# ESP32_wroom_board.net
KiCad netlist of a schematic drawn in Altium Designer
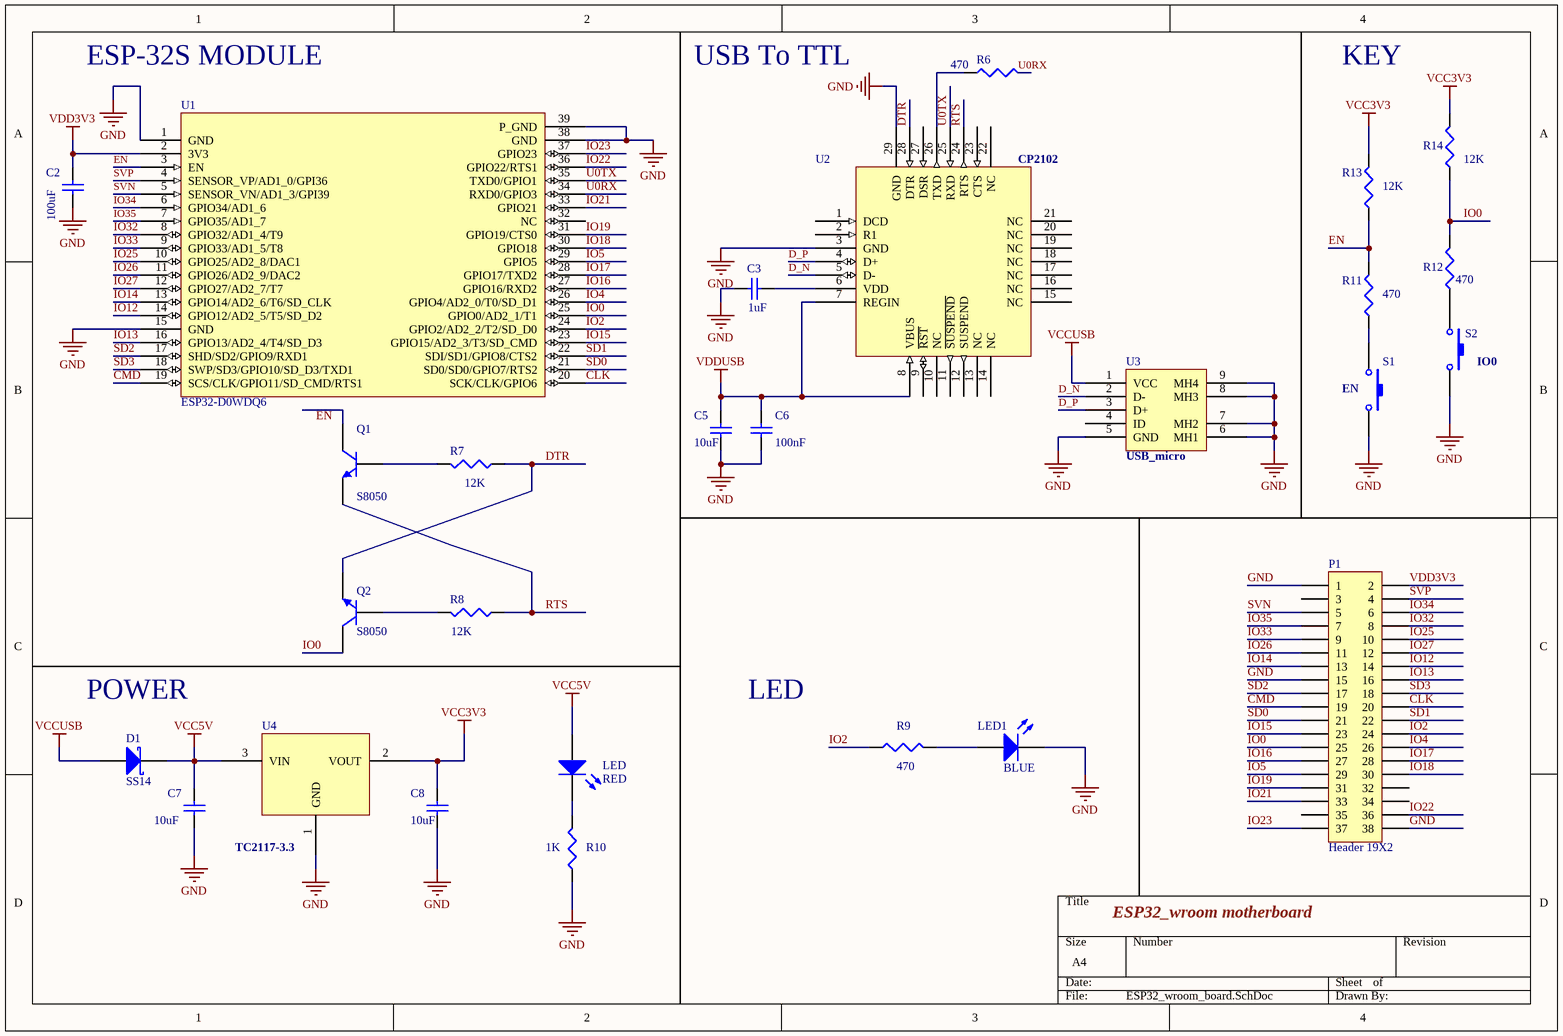
[diagram p0: ESP32_wroom_board.SchDoc]

(export (version "E")
  (design (tool "Eeschema 10.0.6"))
  (components
    (comp (ref "C2")
      (value "100uF")
      (footprint "1608[0603]")
      (description "Capacitor (Semiconductor SIM Model)")
      (fields (field (name "Comment") "Cap Semi") (field (name "PUBLISHER") "Altium Limited"))
      (libsource (lib "Miscellaneous Devices") (part "Cap Semi"))
    )
    (comp (ref "C3")
      (value "1uF")
      (footprint "1608[0603]")
      (description "Capacitor (Semiconductor SIM Model)")
      (fields (field (name "Comment") "Cap Semi") (field (name "PUBLISHER") "Altium Limited"))
      (libsource (lib "Miscellaneous Devices") (part "Cap Semi"))
    )
    (comp (ref "C5")
      (value "10uF")
      (footprint "1608[0603]")
      (description "Capacitor (Semiconductor SIM Model)")
      (fields (field (name "Comment") "Cap Semi") (field (name "PUBLISHER") "Altium Limited"))
      (libsource (lib "Miscellaneous Devices") (part "Cap Semi"))
    )
    (comp (ref "C6")
      (value "100nF")
      (footprint "1608[0603]")
      (description "Capacitor (Semiconductor SIM Model)")
      (fields (field (name "Comment") "Cap Semi") (field (name "PUBLISHER") "Altium Limited"))
      (libsource (lib "Miscellaneous Devices") (part "Cap Semi"))
    )
    (comp (ref "C7")
      (value "10uF")
      (footprint "1608[0603]")
      (description "Capacitor (Semiconductor SIM Model)")
      (fields (field (name "Comment") "Cap Semi") (field (name "PUBLISHER") "Altium Limited"))
      (libsource (lib "Miscellaneous Devices") (part "Cap Semi"))
    )
    (comp (ref "C8")
      (value "10uF")
      (footprint "1608[0603]")
      (description "Capacitor (Semiconductor SIM Model)")
      (fields (field (name "Comment") "Cap Semi") (field (name "PUBLISHER") "Altium Limited"))
      (libsource (lib "Miscellaneous Devices") (part "Cap Semi"))
    )
    (comp (ref "D1")
      (value "SS14")
      (footprint "SOD323")
      (description "Schottky Barrier Diode")
      (fields (field (name "PUBLISHER") "Altium Limited"))
      (libsource (lib "Philips Discrete Diode - Schottky") (part "BAT760"))
    )
    (comp (ref "LED")
      (value "RED")
      (footprint "3.2X1.6X1.1")
      (description "Typical RED, GREEN, YELLOW, AMBER GaAs LED")
      (fields (field (name "PUBLISHER") "Altium Limited"))
      (libsource (lib "Miscellaneous Devices") (part "LED2"))
    )
    (comp (ref "LED1")
      (value "BLUE")
      (footprint "3.2X1.6X1.1")
      (description "Typical RED, GREEN, YELLOW, AMBER GaAs LED")
      (fields (field (name "PUBLISHER") "Altium Limited"))
      (libsource (lib "Miscellaneous Devices") (part "LED2"))
    )
    (comp (ref "P1")
      (value "Header 19X2")
      (footprint "HDR2X19")
      (description "Header, 19-Pin, Dual row")
      (fields (field (name "PUBLISHER") "Altium Limited"))
      (libsource (lib "Miscellaneous Connectors") (part "Header 19X2"))
    )
    (comp (ref "Q1")
      (value "S8050")
      (footprint "SOT-23A_N")
      (description "NPN General Purpose Amplifier")
      (fields (field (name "PUBLISHER") "Altium Limited"))
      (libsource (lib "FSC Discrete BJT") (part "BCW65C"))
    )
    (comp (ref "Q2")
      (value "S8050")
      (footprint "SOT-23A_N")
      (description "NPN General Purpose Amplifier")
      (fields (field (name "PUBLISHER") "Altium Limited"))
      (libsource (lib "FSC Discrete BJT") (part "BCW65C"))
    )
    (comp (ref "R6")
      (value "470")
      (footprint "J1-0603")
      (description "Resistor")
      (fields (field (name "Comment") "Res3") (field (name "PUBLISHER") "Altium Limited"))
      (libsource (lib "Miscellaneous Devices") (part "Res3"))
    )
    (comp (ref "R7")
      (value "12K")
      (footprint "J1-0603")
      (description "Resistor")
      (fields (field (name "Comment") "Res3") (field (name "PUBLISHER") "Altium Limited"))
      (libsource (lib "Miscellaneous Devices") (part "Res3"))
    )
    (comp (ref "R8")
      (value "12K")
      (footprint "J1-0603")
      (description "Resistor")
      (fields (field (name "Comment") "Res3") (field (name "PUBLISHER") "Altium Limited"))
      (libsource (lib "Miscellaneous Devices") (part "Res3"))
    )
    (comp (ref "R9")
      (value "470")
      (footprint "J1-0603")
      (description "Resistor")
      (fields (field (name "Comment") "Res3") (field (name "PUBLISHER") "Altium Limited"))
      (libsource (lib "Miscellaneous Devices") (part "Res3"))
    )
    (comp (ref "R10")
      (value "1K")
      (footprint "J1-0603")
      (description "Resistor")
      (fields (field (name "Comment") "Res3") (field (name "PUBLISHER") "Altium Limited"))
      (libsource (lib "Miscellaneous Devices") (part "Res3"))
    )
    (comp (ref "R11")
      (value "470")
      (footprint "J1-0603")
      (description "Resistor")
      (fields (field (name "Comment") "Res3") (field (name "PUBLISHER") "Altium Limited"))
      (libsource (lib "Miscellaneous Devices") (part "Res3"))
    )
    (comp (ref "R12")
      (value "470")
      (footprint "J1-0603")
      (description "Resistor")
      (fields (field (name "Comment") "Res3") (field (name "PUBLISHER") "Altium Limited"))
      (libsource (lib "Miscellaneous Devices") (part "Res3"))
    )
    (comp (ref "R13")
      (value "12K")
      (footprint "J1-0603")
      (description "Resistor")
      (fields (field (name "Comment") "Res3") (field (name "PUBLISHER") "Altium Limited"))
      (libsource (lib "Miscellaneous Devices") (part "Res3"))
    )
    (comp (ref "R14")
      (value "12K")
      (footprint "J1-0603")
      (description "Resistor")
      (fields (field (name "Comment") "Res3") (field (name "PUBLISHER") "Altium Limited"))
      (libsource (lib "Miscellaneous Devices") (part "Res3"))
    )
    (comp (ref "S1")
      (value "SW-PB")
      (footprint "SPST-2")
      (description "Switch")
      (fields (field (name "PUBLISHER") "Altium Limited"))
      (libsource (lib "Miscellaneous Devices") (part "SW-PB"))
    )
    (comp (ref "S2")
      (value "SW-PB")
      (footprint "SPST-2")
      (description "Switch")
      (fields (field (name "PUBLISHER") "Altium Limited"))
      (libsource (lib "Miscellaneous Devices") (part "SW-PB"))
    )
    (comp (ref "U1")
      (value "ESP32-D0WDQ6")
      (footprint "ESP32WROOM32D")
      (libsource (lib "Custom_components") (part "ESP32-WROOM-32"))
    )
    (comp (ref "U2")
      (value "CP2102")
      (description "USB Interface IC USB to UART Bridge QFN28")
      (libsource (lib "Custom_components") (part "CP2102"))
    )
    (comp (ref "U3")
      (value "USB_micro")
      (description "USB_micro_5S_B")
      (libsource (lib "Custom_components") (part "USB_micro"))
    )
    (comp (ref "U4")
      (value "TC2117-3.3")
      (footprint "*SOT230P700X180-4N")
      (description "LDO Voltage Regulators 800mA Fixed Output")
      (libsource (lib "Custom_components") (part "TC2117-3.3VDBTR"))
    )
  )
  (nets
    (net (code "1") (name "/CLK") (class "Default")
      (node (ref "P1") (pin "20") (pinfunction "20_20") (pintype "passive"))
      (node (ref "U1") (pin "20") (pinfunction "SCK/CLK/GPIO6_20") (pintype "bidirectional"))
    )
    (net (code "2") (name "/CMD") (class "Default")
      (node (ref "P1") (pin "19") (pinfunction "19_19") (pintype "passive"))
      (node (ref "U1") (pin "19") (pinfunction "SCS/CLK/GPIO11/SD_CMD/RTS1_19") (pintype "bidirectional"))
    )
    (net (code "3") (name "/DTR") (class "Default")
      (node (ref "Q2") (pin "2") (pinfunction "E_2") (pintype "passive"))
      (node (ref "R7") (pin "1") (pinfunction "1_1") (pintype "passive"))
      (node (ref "U2") (pin "28") (pinfunction "DTR_28") (pintype "input"))
    )
    (net (code "4") (name "/D_N") (class "Default")
      (node (ref "U2") (pin "5") (pinfunction "D-_5") (pintype "bidirectional"))
      (node (ref "U3") (pin "2") (pinfunction "D-_2") (pintype "passive"))
    )
    (net (code "5") (name "/D_P") (class "Default")
      (node (ref "U2") (pin "4") (pinfunction "D+_4") (pintype "bidirectional"))
      (node (ref "U3") (pin "3") (pinfunction "D+_3") (pintype "passive"))
    )
    (net (code "6") (name "/EN") (class "Default")
      (node (ref "R11") (pin "2") (pinfunction "2_2") (pintype "passive"))
      (node (ref "R13") (pin "1") (pinfunction "1_1") (pintype "passive"))
      (node (ref "U1") (pin "3") (pinfunction "EN_3") (pintype "input"))
    )
    (net (code "7") (name "/IO0") (class "Default")
      (node (ref "P1") (pin "25") (pinfunction "25_25") (pintype "passive"))
      (node (ref "Q2") (pin "3") (pinfunction "C_3") (pintype "passive"))
      (node (ref "R12") (pin "2") (pinfunction "2_2") (pintype "passive"))
      (node (ref "R14") (pin "1") (pinfunction "1_1") (pintype "passive"))
      (node (ref "U1") (pin "25") (pinfunction "GPIO0/AD2_1/T1_25") (pintype "bidirectional"))
    )
    (net (code "8") (name "/IO2") (class "Default")
      (node (ref "P1") (pin "24") (pinfunction "24_24") (pintype "passive"))
      (node (ref "R9") (pin "1") (pinfunction "1_1") (pintype "passive"))
      (node (ref "U1") (pin "24") (pinfunction "GPIO2/AD2_2/T2/SD_D0_24") (pintype "bidirectional"))
    )
    (net (code "9") (name "/IO4") (class "Default")
      (node (ref "P1") (pin "26") (pinfunction "26_26") (pintype "passive"))
      (node (ref "U1") (pin "26") (pinfunction "GPIO4/AD2_0/T0/SD_D1_26") (pintype "bidirectional"))
    )
    (net (code "10") (name "/IO5") (class "Default")
      (node (ref "P1") (pin "29") (pinfunction "29_29") (pintype "passive"))
      (node (ref "U1") (pin "29") (pinfunction "GPIO5_29") (pintype "bidirectional"))
    )
    (net (code "11") (name "/IO12") (class "Default")
      (node (ref "P1") (pin "14") (pinfunction "14_14") (pintype "passive"))
      (node (ref "U1") (pin "14") (pinfunction "GPIO12/AD2_5/T5/SD_D2_14") (pintype "bidirectional"))
    )
    (net (code "12") (name "/IO13") (class "Default")
      (node (ref "P1") (pin "16") (pinfunction "16_16") (pintype "passive"))
      (node (ref "U1") (pin "16") (pinfunction "GPIO13/AD2_4/T4/SD_D3_16") (pintype "bidirectional"))
    )
    (net (code "13") (name "/IO14") (class "Default")
      (node (ref "P1") (pin "13") (pinfunction "13_13") (pintype "passive"))
      (node (ref "U1") (pin "13") (pinfunction "GPIO14/AD2_6/T6/SD_CLK_13") (pintype "bidirectional"))
    )
    (net (code "14") (name "/IO15") (class "Default")
      (node (ref "P1") (pin "23") (pinfunction "23_23") (pintype "passive"))
      (node (ref "U1") (pin "23") (pinfunction "GPIO15/AD2_3/T3/SD_CMD_23") (pintype "bidirectional"))
    )
    (net (code "15") (name "/IO16") (class "Default")
      (node (ref "P1") (pin "27") (pinfunction "27_27") (pintype "passive"))
      (node (ref "U1") (pin "27") (pinfunction "GPIO16/RXD2_27") (pintype "bidirectional"))
    )
    (net (code "16") (name "/IO17") (class "Default")
      (node (ref "P1") (pin "28") (pinfunction "28_28") (pintype "passive"))
      (node (ref "U1") (pin "28") (pinfunction "GPIO17/TXD2_28") (pintype "bidirectional"))
    )
    (net (code "17") (name "/IO18") (class "Default")
      (node (ref "P1") (pin "30") (pinfunction "30_30") (pintype "passive"))
      (node (ref "U1") (pin "30") (pinfunction "GPIO18_30") (pintype "bidirectional"))
    )
    (net (code "18") (name "/IO19") (class "Default")
      (node (ref "P1") (pin "31") (pinfunction "31_31") (pintype "passive"))
      (node (ref "U1") (pin "31") (pinfunction "GPIO19/CTS0_31") (pintype "bidirectional"))
    )
    (net (code "19") (name "/IO21") (class "Default")
      (node (ref "P1") (pin "33") (pinfunction "33_33") (pintype "passive"))
      (node (ref "U1") (pin "33") (pinfunction "GPIO21_33") (pintype "bidirectional"))
    )
    (net (code "20") (name "/IO22") (class "Default")
      (node (ref "P1") (pin "36") (pinfunction "36_36") (pintype "passive"))
      (node (ref "U1") (pin "36") (pinfunction "GPIO22/RTS1_36") (pintype "bidirectional"))
    )
    (net (code "21") (name "/IO23") (class "Default")
      (node (ref "P1") (pin "37") (pinfunction "37_37") (pintype "passive"))
      (node (ref "U1") (pin "37") (pinfunction "GPIO23_37") (pintype "bidirectional"))
    )
    (net (code "22") (name "/IO25") (class "Default")
      (node (ref "P1") (pin "10") (pinfunction "10_10") (pintype "passive"))
      (node (ref "U1") (pin "10") (pinfunction "GPIO25/AD2_8/DAC1_10") (pintype "bidirectional"))
    )
    (net (code "23") (name "/IO26") (class "Default")
      (node (ref "P1") (pin "11") (pinfunction "11_11") (pintype "passive"))
      (node (ref "U1") (pin "11") (pinfunction "GPIO26/AD2_9/DAC2_11") (pintype "bidirectional"))
    )
    (net (code "24") (name "/IO27") (class "Default")
      (node (ref "P1") (pin "12") (pinfunction "12_12") (pintype "passive"))
      (node (ref "U1") (pin "12") (pinfunction "GPIO27/AD2_7/T7_12") (pintype "bidirectional"))
    )
    (net (code "25") (name "/IO32") (class "Default")
      (node (ref "P1") (pin "8") (pinfunction "8_8") (pintype "passive"))
      (node (ref "U1") (pin "8") (pinfunction "GPIO32/AD1_4/T9_8") (pintype "bidirectional"))
    )
    (net (code "26") (name "/IO33") (class "Default")
      (node (ref "P1") (pin "9") (pinfunction "9_9") (pintype "passive"))
      (node (ref "U1") (pin "9") (pinfunction "GPIO33/AD1_5/T8_9") (pintype "bidirectional"))
    )
    (net (code "27") (name "/IO34") (class "Default")
      (node (ref "P1") (pin "6") (pinfunction "6_6") (pintype "passive"))
      (node (ref "U1") (pin "6") (pinfunction "GPIO34/AD1_6_6") (pintype "input"))
    )
    (net (code "28") (name "/IO35") (class "Default")
      (node (ref "P1") (pin "7") (pinfunction "7_7") (pintype "passive"))
      (node (ref "U1") (pin "7") (pinfunction "GPIO35/AD1_7_7") (pintype "input"))
    )
    (net (code "29") (name "/RTS") (class "Default")
      (node (ref "Q1") (pin "2") (pinfunction "E_2") (pintype "passive"))
      (node (ref "R8") (pin "1") (pinfunction "1_1") (pintype "passive"))
      (node (ref "U2") (pin "24") (pinfunction "RTS_24") (pintype "output"))
    )
    (net (code "30") (name "/SD0") (class "Default")
      (node (ref "P1") (pin "21") (pinfunction "21_21") (pintype "passive"))
      (node (ref "U1") (pin "21") (pinfunction "SD0/SD0/GPIO7/RTS2_21") (pintype "bidirectional"))
    )
    (net (code "31") (name "/SD1") (class "Default")
      (node (ref "P1") (pin "22") (pinfunction "22_22") (pintype "passive"))
      (node (ref "U1") (pin "22") (pinfunction "SDI/SD1/GPIO8/CTS2_22") (pintype "bidirectional"))
    )
    (net (code "32") (name "/SD2") (class "Default")
      (node (ref "P1") (pin "17") (pinfunction "17_17") (pintype "passive"))
      (node (ref "U1") (pin "17") (pinfunction "SHD/SD2/GPIO9/RXD1_17") (pintype "bidirectional"))
    )
    (net (code "33") (name "/SD3") (class "Default")
      (node (ref "P1") (pin "18") (pinfunction "18_18") (pintype "passive"))
      (node (ref "U1") (pin "18") (pinfunction "SWP/SD3/GPIO10/SD_D3/TXD1_18") (pintype "bidirectional"))
    )
    (net (code "34") (name "/SVN") (class "Default")
      (node (ref "P1") (pin "5") (pinfunction "5_5") (pintype "passive"))
      (node (ref "U1") (pin "5") (pinfunction "SENSOR_VN/AD1_3/GPI39_5") (pintype "input"))
    )
    (net (code "35") (name "/SVP") (class "Default")
      (node (ref "P1") (pin "4") (pinfunction "4_4") (pintype "passive"))
      (node (ref "U1") (pin "4") (pinfunction "SENSOR_VP/AD1_0/GPI36_4") (pintype "input"))
    )
    (net (code "36") (name "/U0RX") (class "Default")
      (node (ref "R6") (pin "2") (pinfunction "2_2") (pintype "passive"))
      (node (ref "U1") (pin "34") (pinfunction "RXD0/GPIO3_34") (pintype "bidirectional"))
    )
    (net (code "37") (name "/U0TX") (class "Default")
      (node (ref "U1") (pin "35") (pinfunction "TXD0/GPIO1_35") (pintype "bidirectional"))
      (node (ref "U2") (pin "25") (pinfunction "RXD_25") (pintype "input"))
    )
    (net (code "38") (name "GND") (class "Default")
      (node (ref "C2") (pin "1") (pinfunction "1_1") (pintype "passive"))
      (node (ref "C3") (pin "1") (pinfunction "1_1") (pintype "passive"))
      (node (ref "C5") (pin "1") (pinfunction "1_1") (pintype "passive"))
      (node (ref "C6") (pin "1") (pinfunction "1_1") (pintype "passive"))
      (node (ref "C7") (pin "2") (pinfunction "2_2") (pintype "passive"))
      (node (ref "C8") (pin "2") (pinfunction "2_2") (pintype "passive"))
      (node (ref "LED1") (pin "2") (pinfunction "K_2") (pintype "passive"))
      (node (ref "P1") (pin "1") (pinfunction "1_1") (pintype "passive"))
      (node (ref "P1") (pin "15") (pinfunction "15_15") (pintype "passive"))
      (node (ref "P1") (pin "38") (pinfunction "38_38") (pintype "passive"))
      (node (ref "R10") (pin "1") (pinfunction "1_1") (pintype "passive"))
      (node (ref "S1") (pin "2") (pinfunction "2_2") (pintype "passive"))
      (node (ref "S2") (pin "2") (pinfunction "2_2") (pintype "passive"))
      (node (ref "U1") (pin "1") (pinfunction "GND_1") (pintype "power_in"))
      (node (ref "U1") (pin "15") (pinfunction "GND_15") (pintype "power_in"))
      (node (ref "U1") (pin "38") (pinfunction "GND_38") (pintype "power_in"))
      (node (ref "U1") (pin "39") (pinfunction "P_GND_39") (pintype "power_in"))
      (node (ref "U2") (pin "29") (pinfunction "GND_29") (pintype "power_in"))
      (node (ref "U2") (pin "3") (pinfunction "GND_3") (pintype "power_in"))
      (node (ref "U3") (pin "5") (pinfunction "GND_5") (pintype "power_in"))
      (node (ref "U3") (pin "6") (pinfunction "MH1_6") (pintype "passive"))
      (node (ref "U3") (pin "7") (pinfunction "MH2_7") (pintype "passive"))
      (node (ref "U3") (pin "8") (pinfunction "MH3_8") (pintype "passive"))
      (node (ref "U3") (pin "9") (pinfunction "MH4_9") (pintype "passive"))
      (node (ref "U4") (pin "1") (pinfunction "GND_1") (pintype "power_in"))
    )
    (net (code "39") (name "Net-(LED-K)") (class "Default")
      (node (ref "LED") (pin "2") (pinfunction "K_2") (pintype "passive"))
      (node (ref "R10") (pin "2") (pinfunction "2_2") (pintype "passive"))
    )
    (net (code "40") (name "Net-(LED1-A)") (class "Default")
      (node (ref "LED1") (pin "1") (pinfunction "A_1") (pintype "passive"))
      (node (ref "R9") (pin "2") (pinfunction "2_2") (pintype "passive"))
    )
    (net (code "41") (name "Net-(Q1-B)") (class "Default")
      (node (ref "Q1") (pin "1") (pinfunction "B_1") (pintype "passive"))
      (node (ref "R7") (pin "2") (pinfunction "2_2") (pintype "passive"))
    )
    (net (code "42") (name "Net-(Q2-B)") (class "Default")
      (node (ref "Q2") (pin "1") (pinfunction "B_1") (pintype "passive"))
      (node (ref "R8") (pin "2") (pinfunction "2_2") (pintype "passive"))
    )
    (net (code "43") (name "Net-(R11-Pad1)") (class "Default")
      (node (ref "R11") (pin "1") (pinfunction "1_1") (pintype "passive"))
      (node (ref "S1") (pin "1") (pinfunction "1_1") (pintype "passive"))
    )
    (net (code "44") (name "Net-(R12-Pad1)") (class "Default")
      (node (ref "R12") (pin "1") (pinfunction "1_1") (pintype "passive"))
      (node (ref "S2") (pin "1") (pinfunction "1_1") (pintype "passive"))
    )
    (net (code "45") (name "Net-(U2-TXD)") (class "Default")
      (node (ref "R6") (pin "1") (pinfunction "1_1") (pintype "passive"))
      (node (ref "U2") (pin "26") (pinfunction "TXD_26") (pintype "output"))
    )
    (net (code "46") (name "Net-(U2-VDD)") (class "Default")
      (node (ref "C3") (pin "2") (pinfunction "2_2") (pintype "passive"))
      (node (ref "U2") (pin "6") (pinfunction "VDD_6") (pintype "passive"))
    )
    (net (code "47") (name "VCC3V3") (class "Default")
      (node (ref "C8") (pin "1") (pinfunction "1_1") (pintype "passive"))
      (node (ref "R13") (pin "2") (pinfunction "2_2") (pintype "passive"))
      (node (ref "R14") (pin "2") (pinfunction "2_2") (pintype "passive"))
      (node (ref "U4") (pin "2") (pinfunction "VOUT_2") (pintype "power_in"))
    )
    (net (code "48") (name "VCC5V") (class "Default")
      (node (ref "C7") (pin "1") (pinfunction "1_1") (pintype "passive"))
      (node (ref "D1") (pin "1") (pinfunction "K_1") (pintype "passive"))
      (node (ref "LED") (pin "1") (pinfunction "A_1") (pintype "passive"))
      (node (ref "U4") (pin "3") (pinfunction "VIN_3") (pintype "power_in"))
    )
    (net (code "49") (name "VCCUSB") (class "Default")
      (node (ref "D1") (pin "2") (pinfunction "A_2") (pintype "passive"))
      (node (ref "U3") (pin "1") (pinfunction "VCC_1") (pintype "power_in"))
    )
    (net (code "50") (name "VDD3V3") (class "Default")
      (node (ref "C2") (pin "2") (pinfunction "2_2") (pintype "passive"))
      (node (ref "P1") (pin "2") (pinfunction "2_2") (pintype "passive"))
      (node (ref "U1") (pin "2") (pinfunction "3V3_2") (pintype "power_in"))
    )
    (net (code "51") (name "VDDUSB") (class "Default")
      (node (ref "C5") (pin "2") (pinfunction "2_2") (pintype "passive"))
      (node (ref "C6") (pin "2") (pinfunction "2_2") (pintype "passive"))
      (node (ref "U2") (pin "7") (pinfunction "REGIN_7") (pintype "passive"))
      (node (ref "U2") (pin "8") (pinfunction "VBUS_8") (pintype "input"))
    )
    (net (code "52") (name "unconnected-(P1-Pad3)") (class "Default")
      (node (ref "P1") (pin "3") (pinfunction "3_3") (pintype "passive"))
    )
    (net (code "53") (name "unconnected-(P1-Pad32)") (class "Default")
      (node (ref "P1") (pin "32") (pinfunction "32_32") (pintype "passive"))
    )
    (net (code "54") (name "unconnected-(P1-Pad34)") (class "Default")
      (node (ref "P1") (pin "34") (pinfunction "34_34") (pintype "passive"))
    )
    (net (code "55") (name "unconnected-(P1-Pad35)") (class "Default")
      (node (ref "P1") (pin "35") (pinfunction "35_35") (pintype "passive"))
    )
    (net (code "56") (name "unconnected-(Q1-C-Pad3)") (class "Default")
      (node (ref "Q1") (pin "3") (pinfunction "C_3") (pintype "passive"))
    )
    (net (code "57") (name "unconnected-(U1-NC-Pad32)") (class "Default")
      (node (ref "U1") (pin "32") (pinfunction "NC_32") (pintype "bidirectional"))
    )
    (net (code "58") (name "unconnected-(U2-CTS-Pad23)") (class "Default")
      (node (ref "U2") (pin "23") (pinfunction "CTS_23") (pintype "input"))
    )
    (net (code "59") (name "unconnected-(U2-DCD-Pad1)") (class "Default")
      (node (ref "U2") (pin "1") (pinfunction "DCD_1") (pintype "input"))
    )
    (net (code "60") (name "unconnected-(U2-DSR-Pad27)") (class "Default")
      (node (ref "U2") (pin "27") (pinfunction "DSR_27") (pintype "input"))
    )
    (net (code "61") (name "unconnected-(U2-NC-Pad10)") (class "Default")
      (node (ref "U2") (pin "10") (pinfunction "NC_10") (pintype "power_in"))
    )
    (net (code "62") (name "unconnected-(U2-NC-Pad13)") (class "Default")
      (node (ref "U2") (pin "13") (pinfunction "NC_13") (pintype "passive"))
    )
    (net (code "63") (name "unconnected-(U2-NC-Pad14)") (class "Default")
      (node (ref "U2") (pin "14") (pinfunction "NC_14") (pintype "passive"))
    )
    (net (code "64") (name "unconnected-(U2-NC-Pad15)") (class "Default")
      (node (ref "U2") (pin "15") (pinfunction "NC_15") (pintype "passive"))
    )
    (net (code "65") (name "unconnected-(U2-NC-Pad16)") (class "Default")
      (node (ref "U2") (pin "16") (pinfunction "NC_16") (pintype "passive"))
    )
    (net (code "66") (name "unconnected-(U2-NC-Pad17)") (class "Default")
      (node (ref "U2") (pin "17") (pinfunction "NC_17") (pintype "passive"))
    )
    (net (code "67") (name "unconnected-(U2-NC-Pad18)") (class "Default")
      (node (ref "U2") (pin "18") (pinfunction "NC_18") (pintype "passive"))
    )
    (net (code "68") (name "unconnected-(U2-NC-Pad19)") (class "Default")
      (node (ref "U2") (pin "19") (pinfunction "NC_19") (pintype "passive"))
    )
    (net (code "69") (name "unconnected-(U2-NC-Pad20)") (class "Default")
      (node (ref "U2") (pin "20") (pinfunction "NC_20") (pintype "passive"))
    )
    (net (code "70") (name "unconnected-(U2-NC-Pad21)") (class "Default")
      (node (ref "U2") (pin "21") (pinfunction "NC_21") (pintype "passive"))
    )
    (net (code "71") (name "unconnected-(U2-NC-Pad22)") (class "Default")
      (node (ref "U2") (pin "22") (pinfunction "NC_22") (pintype "passive"))
    )
    (net (code "72") (name "unconnected-(U2-R1-Pad2)") (class "Default")
      (node (ref "U2") (pin "2") (pinfunction "R1_2") (pintype "input"))
    )
    (net (code "73") (name "unconnected-(U2-SUSPEND-Pad12)") (class "Default")
      (node (ref "U2") (pin "12") (pinfunction "SUSPEND_12") (pintype "output"))
    )
    (net (code "74") (name "unconnected-(U2-~{RST}-Pad9)") (class "Default")
      (node (ref "U2") (pin "9") (pinfunction "~{RST}_9") (pintype "bidirectional"))
    )
    (net (code "75") (name "unconnected-(U2-~{SUSPEND}-Pad11)") (class "Default")
      (node (ref "U2") (pin "11") (pinfunction "~{SUSPEND}_11") (pintype "output"))
    )
    (net (code "76") (name "unconnected-(U3-ID-Pad4)") (class "Default")
      (node (ref "U3") (pin "4") (pinfunction "ID_4") (pintype "passive"))
    )
  )
)
